# PCE_Joypad_Breakout-v3.net
KiCad netlist of a schematic drawn in EAGLE
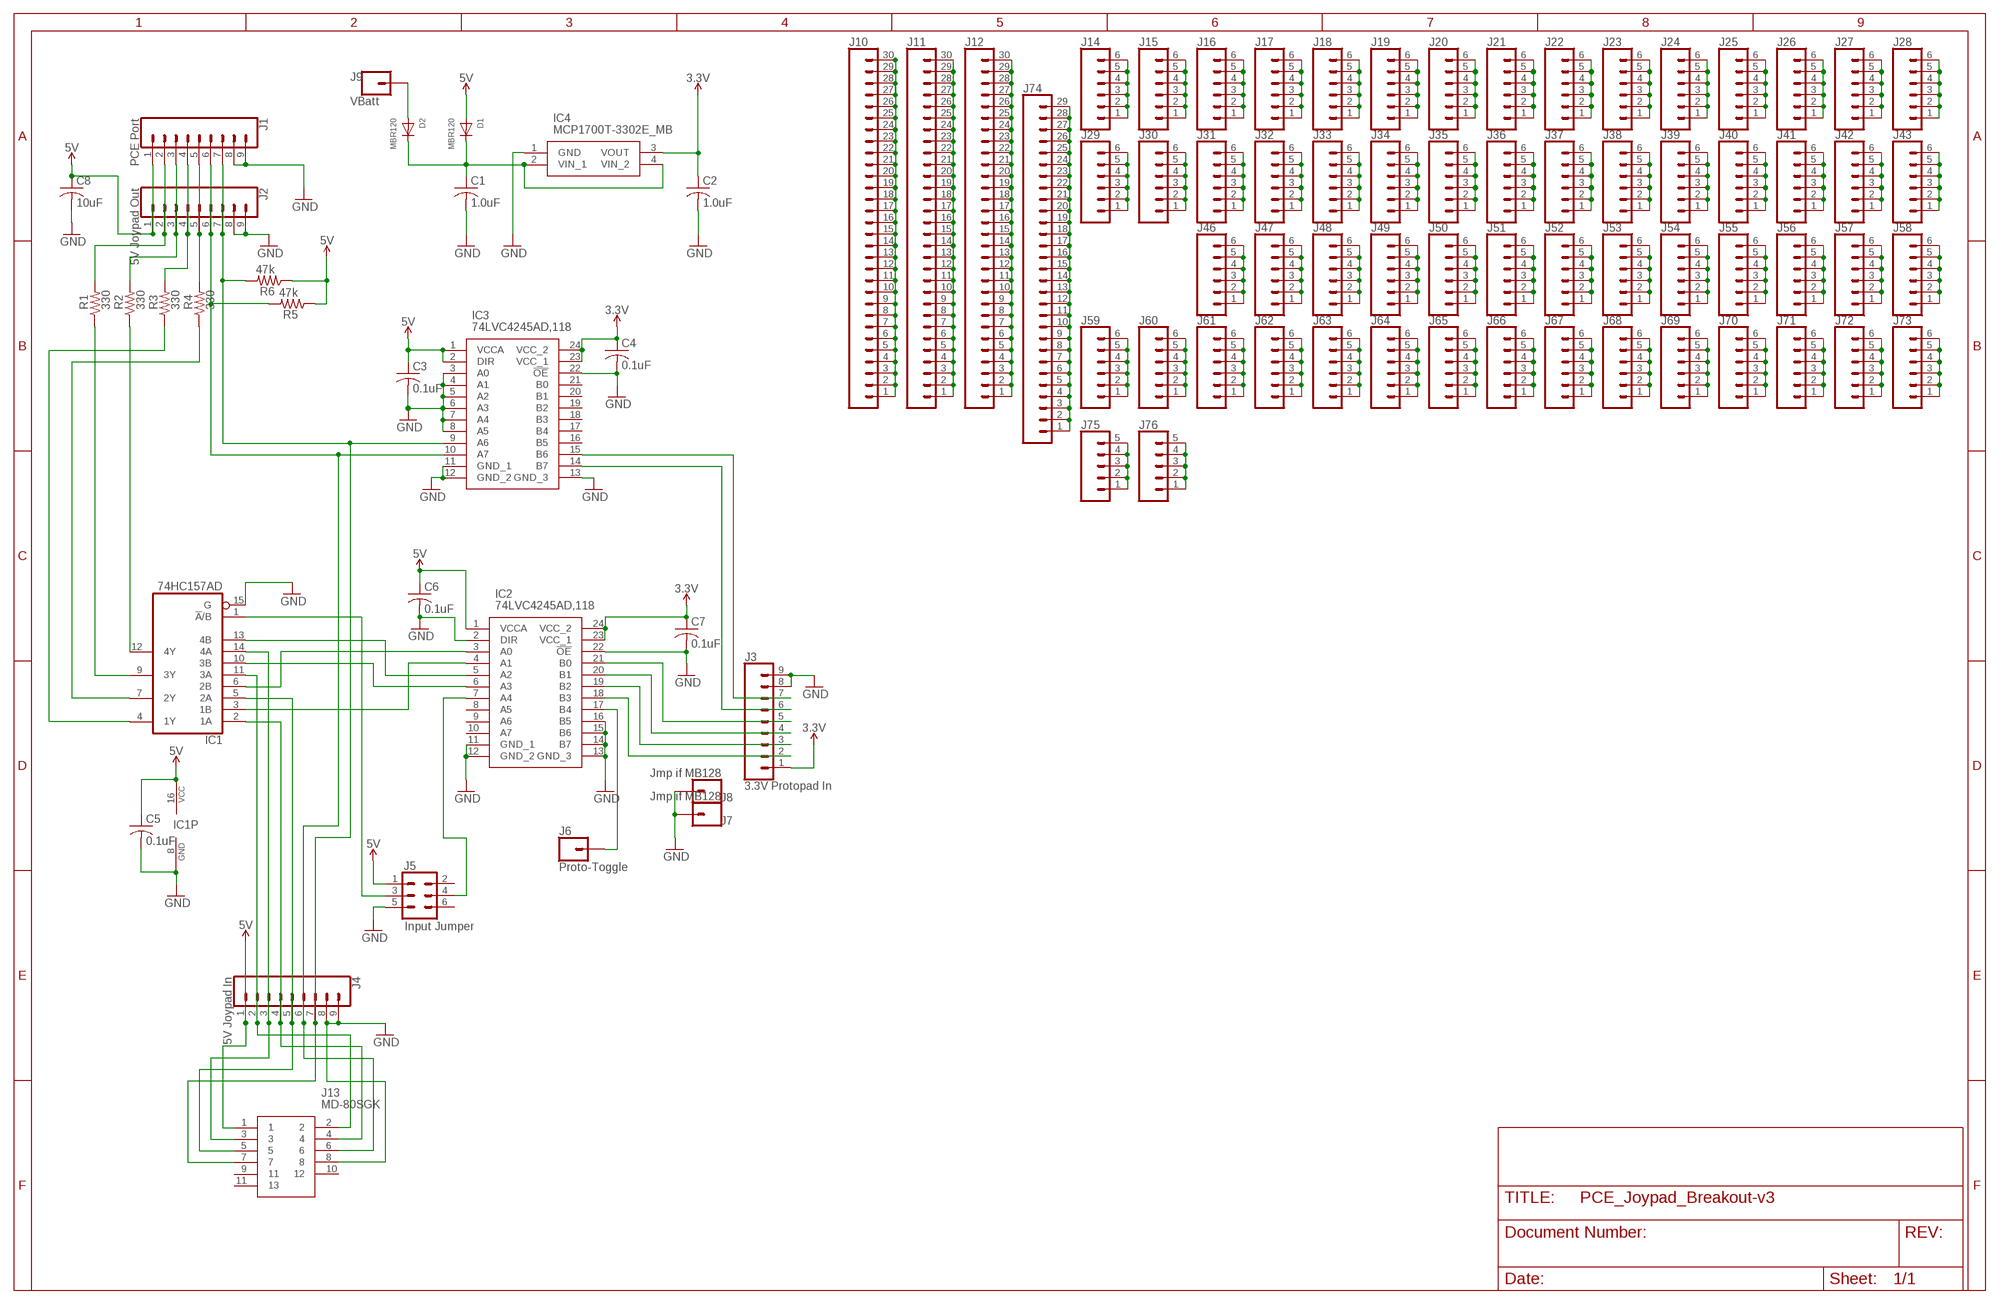
[diagram p0: schematic, sheet 1]

(export (version "E")
  (design (tool "Eeschema 10.0.6"))
  (components
    (comp (ref "C1")
      (value "1.0uF")
      (footprint "eagle-import:C0805")
      (libsource (lib "eagle-import") (part "C-USC0805"))
    )
    (comp (ref "C2")
      (value "1.0uF")
      (footprint "eagle-import:C0805")
      (libsource (lib "eagle-import") (part "C-USC0805"))
    )
    (comp (ref "C3")
      (value "0.1uF")
      (footprint "eagle-import:C0805")
      (libsource (lib "eagle-import") (part "C-USC0805"))
    )
    (comp (ref "C4")
      (value "0.1uF")
      (footprint "eagle-import:C0805")
      (libsource (lib "eagle-import") (part "C-USC0805"))
    )
    (comp (ref "C5")
      (value "0.1uF")
      (footprint "eagle-import:C0805")
      (libsource (lib "eagle-import") (part "C-USC0805"))
    )
    (comp (ref "C6")
      (value "0.1uF")
      (footprint "eagle-import:C0805")
      (libsource (lib "eagle-import") (part "C-USC0805"))
    )
    (comp (ref "C7")
      (value "0.1uF")
      (footprint "eagle-import:C0805")
      (libsource (lib "eagle-import") (part "C-USC0805"))
    )
    (comp (ref "C8")
      (value "10uF")
      (footprint "eagle-import:C0805")
      (libsource (lib "eagle-import") (part "C-USC0805"))
    )
    (comp (ref "D1")
      (value "MBR120")
      (footprint "eagle-import:SOD-123")
      (libsource (lib "eagle-import") (part "DIODESOD-123"))
    )
    (comp (ref "D2")
      (value "MBR120")
      (footprint "eagle-import:SOD-123")
      (libsource (lib "eagle-import") (part "DIODESOD-123"))
    )
    (comp (ref "IC1")
      (value "74HC157AD")
      (footprint "eagle-import:SO16")
      (libsource (lib "eagle-import") (part "74157D"))
    )
    (comp (ref "IC2")
      (value "74LVC4245AD,118")
      (footprint "eagle-import:SOIC127P1032X265-24N")
      (fields
        (field (name "MOUSER_PART_NUMBER") "771-74LVC4245AD-T")
        (field (name "RS_PART_NUMBER") "1708039")
      )
      (libsource (lib "eagle-import") (part "74LVC4245AD,118"))
    )
    (comp (ref "IC3")
      (value "74LVC4245AD,118")
      (footprint "eagle-import:SOIC127P1032X265-24N")
      (fields
        (field (name "MOUSER_PART_NUMBER") "771-74LVC4245AD-T")
        (field (name "RS_PART_NUMBER") "1708039")
      )
      (libsource (lib "eagle-import") (part "74LVC4245AD,118"))
    )
    (comp (ref "IC4")
      (value "MCP1700T-3302E_MB")
      (footprint "eagle-import:MCP1700T-3302E_MB")
      (fields
        (field (name "MANUFACTURER_PART_NUMBER") "MCP1700T-3302E/MB")
        (field (name "MOUSER_PART_NUMBER") "579-MCP1700T3302E/MB")
        (field (name "RS_PART_NUMBER") "9115561")
      )
      (libsource (lib "eagle-import") (part "MCP1700T-3302E_MB"))
    )
    (comp (ref "J1")
      (value "PCE Port")
      (footprint "eagle-import:1X09")
      (libsource (lib "eagle-import") (part "CONN_09"))
    )
    (comp (ref "J2")
      (value "5V Joypad Out")
      (footprint "eagle-import:1X09")
      (libsource (lib "eagle-import") (part "CONN_09"))
    )
    (comp (ref "J3")
      (value "3.3V Protopad In")
      (footprint "eagle-import:1X09")
      (libsource (lib "eagle-import") (part "CONN_09"))
    )
    (comp (ref "J4")
      (value "5V Joypad In")
      (footprint "eagle-import:1X09")
      (libsource (lib "eagle-import") (part "CONN_09"))
    )
    (comp (ref "J5")
      (value "Input Jumper")
      (footprint "eagle-import:2X3")
      (libsource (lib "eagle-import") (part "CONN_03X2FEMALE"))
    )
    (comp (ref "J6")
      (value "Proto-Toggle")
      (footprint "eagle-import:1X01")
      (libsource (lib "eagle-import") (part "CONN_01"))
    )
    (comp (ref "J7")
      (value "Jmp if MB128")
      (footprint "eagle-import:1X01")
      (libsource (lib "eagle-import") (part "CONN_01"))
    )
    (comp (ref "J8")
      (value "Jmp if MB128")
      (footprint "eagle-import:1X01")
      (libsource (lib "eagle-import") (part "CONN_01"))
    )
    (comp (ref "J9")
      (value "VBatt")
      (footprint "eagle-import:1X01")
      (libsource (lib "eagle-import") (part "CONN_01"))
    )
    (comp (ref "J10")
      (value "CONN_30NO_SILK")
      (footprint "eagle-import:1X30_NO_SILK")
      (libsource (lib "eagle-import") (part "CONN_30NO_SILK"))
    )
    (comp (ref "J11")
      (value "CONN_30NO_SILK")
      (footprint "eagle-import:1X30_NO_SILK")
      (libsource (lib "eagle-import") (part "CONN_30NO_SILK"))
    )
    (comp (ref "J12")
      (value "CONN_30NO_SILK")
      (footprint "eagle-import:1X30_NO_SILK")
      (libsource (lib "eagle-import") (part "CONN_30NO_SILK"))
    )
    (comp (ref "J13")
      (value "MD-80SGK")
      (footprint "eagle-import:MD80SGK")
      (fields (field (name "MOUSER_PART_NUMBER") "490-MD-80SGK"))
      (libsource (lib "eagle-import") (part "MD-80SGK"))
    )
    (comp (ref "J14")
      (value "CONN_06NO_SILK_FEMALE_PTH")
      (footprint "eagle-import:1X06_NO_SILK")
      (libsource (lib "eagle-import") (part "CONN_06NO_SILK_FEMALE_PTH"))
    )
    (comp (ref "J15")
      (value "CONN_06NO_SILK_FEMALE_PTH")
      (footprint "eagle-import:1X06_NO_SILK")
      (libsource (lib "eagle-import") (part "CONN_06NO_SILK_FEMALE_PTH"))
    )
    (comp (ref "J16")
      (value "CONN_06NO_SILK_FEMALE_PTH")
      (footprint "eagle-import:1X06_NO_SILK")
      (libsource (lib "eagle-import") (part "CONN_06NO_SILK_FEMALE_PTH"))
    )
    (comp (ref "J17")
      (value "CONN_06NO_SILK_FEMALE_PTH")
      (footprint "eagle-import:1X06_NO_SILK")
      (libsource (lib "eagle-import") (part "CONN_06NO_SILK_FEMALE_PTH"))
    )
    (comp (ref "J18")
      (value "CONN_06NO_SILK_FEMALE_PTH")
      (footprint "eagle-import:1X06_NO_SILK")
      (libsource (lib "eagle-import") (part "CONN_06NO_SILK_FEMALE_PTH"))
    )
    (comp (ref "J19")
      (value "CONN_06NO_SILK_FEMALE_PTH")
      (footprint "eagle-import:1X06_NO_SILK")
      (libsource (lib "eagle-import") (part "CONN_06NO_SILK_FEMALE_PTH"))
    )
    (comp (ref "J20")
      (value "CONN_06NO_SILK_FEMALE_PTH")
      (footprint "eagle-import:1X06_NO_SILK")
      (libsource (lib "eagle-import") (part "CONN_06NO_SILK_FEMALE_PTH"))
    )
    (comp (ref "J21")
      (value "CONN_06NO_SILK_FEMALE_PTH")
      (footprint "eagle-import:1X06_NO_SILK")
      (libsource (lib "eagle-import") (part "CONN_06NO_SILK_FEMALE_PTH"))
    )
    (comp (ref "J22")
      (value "CONN_06NO_SILK_FEMALE_PTH")
      (footprint "eagle-import:1X06_NO_SILK")
      (libsource (lib "eagle-import") (part "CONN_06NO_SILK_FEMALE_PTH"))
    )
    (comp (ref "J23")
      (value "CONN_06NO_SILK_FEMALE_PTH")
      (footprint "eagle-import:1X06_NO_SILK")
      (libsource (lib "eagle-import") (part "CONN_06NO_SILK_FEMALE_PTH"))
    )
    (comp (ref "J24")
      (value "CONN_06NO_SILK_FEMALE_PTH")
      (footprint "eagle-import:1X06_NO_SILK")
      (libsource (lib "eagle-import") (part "CONN_06NO_SILK_FEMALE_PTH"))
    )
    (comp (ref "J25")
      (value "CONN_06NO_SILK_FEMALE_PTH")
      (footprint "eagle-import:1X06_NO_SILK")
      (libsource (lib "eagle-import") (part "CONN_06NO_SILK_FEMALE_PTH"))
    )
    (comp (ref "J26")
      (value "CONN_06NO_SILK_FEMALE_PTH")
      (footprint "eagle-import:1X06_NO_SILK")
      (libsource (lib "eagle-import") (part "CONN_06NO_SILK_FEMALE_PTH"))
    )
    (comp (ref "J27")
      (value "CONN_06NO_SILK_FEMALE_PTH")
      (footprint "eagle-import:1X06_NO_SILK")
      (libsource (lib "eagle-import") (part "CONN_06NO_SILK_FEMALE_PTH"))
    )
    (comp (ref "J28")
      (value "CONN_06NO_SILK_FEMALE_PTH")
      (footprint "eagle-import:1X06_NO_SILK")
      (libsource (lib "eagle-import") (part "CONN_06NO_SILK_FEMALE_PTH"))
    )
    (comp (ref "J29")
      (value "CONN_06NO_SILK_FEMALE_PTH")
      (footprint "eagle-import:1X06_NO_SILK")
      (libsource (lib "eagle-import") (part "CONN_06NO_SILK_FEMALE_PTH"))
    )
    (comp (ref "J30")
      (value "CONN_06NO_SILK_FEMALE_PTH")
      (footprint "eagle-import:1X06_NO_SILK")
      (libsource (lib "eagle-import") (part "CONN_06NO_SILK_FEMALE_PTH"))
    )
    (comp (ref "J31")
      (value "CONN_06NO_SILK_FEMALE_PTH")
      (footprint "eagle-import:1X06_NO_SILK")
      (libsource (lib "eagle-import") (part "CONN_06NO_SILK_FEMALE_PTH"))
    )
    (comp (ref "J32")
      (value "CONN_06NO_SILK_FEMALE_PTH")
      (footprint "eagle-import:1X06_NO_SILK")
      (libsource (lib "eagle-import") (part "CONN_06NO_SILK_FEMALE_PTH"))
    )
    (comp (ref "J33")
      (value "CONN_06NO_SILK_FEMALE_PTH")
      (footprint "eagle-import:1X06_NO_SILK")
      (libsource (lib "eagle-import") (part "CONN_06NO_SILK_FEMALE_PTH"))
    )
    (comp (ref "J34")
      (value "CONN_06NO_SILK_FEMALE_PTH")
      (footprint "eagle-import:1X06_NO_SILK")
      (libsource (lib "eagle-import") (part "CONN_06NO_SILK_FEMALE_PTH"))
    )
    (comp (ref "J35")
      (value "CONN_06NO_SILK_FEMALE_PTH")
      (footprint "eagle-import:1X06_NO_SILK")
      (libsource (lib "eagle-import") (part "CONN_06NO_SILK_FEMALE_PTH"))
    )
    (comp (ref "J36")
      (value "CONN_06NO_SILK_FEMALE_PTH")
      (footprint "eagle-import:1X06_NO_SILK")
      (libsource (lib "eagle-import") (part "CONN_06NO_SILK_FEMALE_PTH"))
    )
    (comp (ref "J37")
      (value "CONN_06NO_SILK_FEMALE_PTH")
      (footprint "eagle-import:1X06_NO_SILK")
      (libsource (lib "eagle-import") (part "CONN_06NO_SILK_FEMALE_PTH"))
    )
    (comp (ref "J38")
      (value "CONN_06NO_SILK_FEMALE_PTH")
      (footprint "eagle-import:1X06_NO_SILK")
      (libsource (lib "eagle-import") (part "CONN_06NO_SILK_FEMALE_PTH"))
    )
    (comp (ref "J39")
      (value "CONN_06NO_SILK_FEMALE_PTH")
      (footprint "eagle-import:1X06_NO_SILK")
      (libsource (lib "eagle-import") (part "CONN_06NO_SILK_FEMALE_PTH"))
    )
    (comp (ref "J40")
      (value "CONN_06NO_SILK_FEMALE_PTH")
      (footprint "eagle-import:1X06_NO_SILK")
      (libsource (lib "eagle-import") (part "CONN_06NO_SILK_FEMALE_PTH"))
    )
    (comp (ref "J41")
      (value "CONN_06NO_SILK_FEMALE_PTH")
      (footprint "eagle-import:1X06_NO_SILK")
      (libsource (lib "eagle-import") (part "CONN_06NO_SILK_FEMALE_PTH"))
    )
    (comp (ref "J42")
      (value "CONN_06NO_SILK_FEMALE_PTH")
      (footprint "eagle-import:1X06_NO_SILK")
      (libsource (lib "eagle-import") (part "CONN_06NO_SILK_FEMALE_PTH"))
    )
    (comp (ref "J43")
      (value "CONN_06NO_SILK_FEMALE_PTH")
      (footprint "eagle-import:1X06_NO_SILK")
      (libsource (lib "eagle-import") (part "CONN_06NO_SILK_FEMALE_PTH"))
    )
    (comp (ref "J46")
      (value "CONN_06NO_SILK_FEMALE_PTH")
      (footprint "eagle-import:1X06_NO_SILK")
      (libsource (lib "eagle-import") (part "CONN_06NO_SILK_FEMALE_PTH"))
    )
    (comp (ref "J47")
      (value "CONN_06NO_SILK_FEMALE_PTH")
      (footprint "eagle-import:1X06_NO_SILK")
      (libsource (lib "eagle-import") (part "CONN_06NO_SILK_FEMALE_PTH"))
    )
    (comp (ref "J48")
      (value "CONN_06NO_SILK_FEMALE_PTH")
      (footprint "eagle-import:1X06_NO_SILK")
      (libsource (lib "eagle-import") (part "CONN_06NO_SILK_FEMALE_PTH"))
    )
    (comp (ref "J49")
      (value "CONN_06NO_SILK_FEMALE_PTH")
      (footprint "eagle-import:1X06_NO_SILK")
      (libsource (lib "eagle-import") (part "CONN_06NO_SILK_FEMALE_PTH"))
    )
    (comp (ref "J50")
      (value "CONN_06NO_SILK_FEMALE_PTH")
      (footprint "eagle-import:1X06_NO_SILK")
      (libsource (lib "eagle-import") (part "CONN_06NO_SILK_FEMALE_PTH"))
    )
    (comp (ref "J51")
      (value "CONN_06NO_SILK_FEMALE_PTH")
      (footprint "eagle-import:1X06_NO_SILK")
      (libsource (lib "eagle-import") (part "CONN_06NO_SILK_FEMALE_PTH"))
    )
    (comp (ref "J52")
      (value "CONN_06NO_SILK_FEMALE_PTH")
      (footprint "eagle-import:1X06_NO_SILK")
      (libsource (lib "eagle-import") (part "CONN_06NO_SILK_FEMALE_PTH"))
    )
    (comp (ref "J53")
      (value "CONN_06NO_SILK_FEMALE_PTH")
      (footprint "eagle-import:1X06_NO_SILK")
      (libsource (lib "eagle-import") (part "CONN_06NO_SILK_FEMALE_PTH"))
    )
    (comp (ref "J54")
      (value "CONN_06NO_SILK_FEMALE_PTH")
      (footprint "eagle-import:1X06_NO_SILK")
      (libsource (lib "eagle-import") (part "CONN_06NO_SILK_FEMALE_PTH"))
    )
    (comp (ref "J55")
      (value "CONN_06NO_SILK_FEMALE_PTH")
      (footprint "eagle-import:1X06_NO_SILK")
      (libsource (lib "eagle-import") (part "CONN_06NO_SILK_FEMALE_PTH"))
    )
    (comp (ref "J56")
      (value "CONN_06NO_SILK_FEMALE_PTH")
      (footprint "eagle-import:1X06_NO_SILK")
      (libsource (lib "eagle-import") (part "CONN_06NO_SILK_FEMALE_PTH"))
    )
    (comp (ref "J57")
      (value "CONN_06NO_SILK_FEMALE_PTH")
      (footprint "eagle-import:1X06_NO_SILK")
      (libsource (lib "eagle-import") (part "CONN_06NO_SILK_FEMALE_PTH"))
    )
    (comp (ref "J58")
      (value "CONN_06NO_SILK_FEMALE_PTH")
      (footprint "eagle-import:1X06_NO_SILK")
      (libsource (lib "eagle-import") (part "CONN_06NO_SILK_FEMALE_PTH"))
    )
    (comp (ref "J59")
      (value "CONN_06NO_SILK_FEMALE_PTH")
      (footprint "eagle-import:1X06_NO_SILK")
      (libsource (lib "eagle-import") (part "CONN_06NO_SILK_FEMALE_PTH"))
    )
    (comp (ref "J60")
      (value "CONN_06NO_SILK_FEMALE_PTH")
      (footprint "eagle-import:1X06_NO_SILK")
      (libsource (lib "eagle-import") (part "CONN_06NO_SILK_FEMALE_PTH"))
    )
    (comp (ref "J61")
      (value "CONN_06NO_SILK_FEMALE_PTH")
      (footprint "eagle-import:1X06_NO_SILK")
      (libsource (lib "eagle-import") (part "CONN_06NO_SILK_FEMALE_PTH"))
    )
    (comp (ref "J62")
      (value "CONN_06NO_SILK_FEMALE_PTH")
      (footprint "eagle-import:1X06_NO_SILK")
      (libsource (lib "eagle-import") (part "CONN_06NO_SILK_FEMALE_PTH"))
    )
    (comp (ref "J63")
      (value "CONN_06NO_SILK_FEMALE_PTH")
      (footprint "eagle-import:1X06_NO_SILK")
      (libsource (lib "eagle-import") (part "CONN_06NO_SILK_FEMALE_PTH"))
    )
    (comp (ref "J64")
      (value "CONN_06NO_SILK_FEMALE_PTH")
      (footprint "eagle-import:1X06_NO_SILK")
      (libsource (lib "eagle-import") (part "CONN_06NO_SILK_FEMALE_PTH"))
    )
    (comp (ref "J65")
      (value "CONN_06NO_SILK_FEMALE_PTH")
      (footprint "eagle-import:1X06_NO_SILK")
      (libsource (lib "eagle-import") (part "CONN_06NO_SILK_FEMALE_PTH"))
    )
    (comp (ref "J66")
      (value "CONN_06NO_SILK_FEMALE_PTH")
      (footprint "eagle-import:1X06_NO_SILK")
      (libsource (lib "eagle-import") (part "CONN_06NO_SILK_FEMALE_PTH"))
    )
    (comp (ref "J67")
      (value "CONN_06NO_SILK_FEMALE_PTH")
      (footprint "eagle-import:1X06_NO_SILK")
      (libsource (lib "eagle-import") (part "CONN_06NO_SILK_FEMALE_PTH"))
    )
    (comp (ref "J68")
      (value "CONN_06NO_SILK_FEMALE_PTH")
      (footprint "eagle-import:1X06_NO_SILK")
      (libsource (lib "eagle-import") (part "CONN_06NO_SILK_FEMALE_PTH"))
    )
    (comp (ref "J69")
      (value "CONN_06NO_SILK_FEMALE_PTH")
      (footprint "eagle-import:1X06_NO_SILK")
      (libsource (lib "eagle-import") (part "CONN_06NO_SILK_FEMALE_PTH"))
    )
    (comp (ref "J70")
      (value "CONN_06NO_SILK_FEMALE_PTH")
      (footprint "eagle-import:1X06_NO_SILK")
      (libsource (lib "eagle-import") (part "CONN_06NO_SILK_FEMALE_PTH"))
    )
    (comp (ref "J71")
      (value "CONN_06NO_SILK_FEMALE_PTH")
      (footprint "eagle-import:1X06_NO_SILK")
      (libsource (lib "eagle-import") (part "CONN_06NO_SILK_FEMALE_PTH"))
    )
    (comp (ref "J72")
      (value "CONN_06NO_SILK_FEMALE_PTH")
      (footprint "eagle-import:1X06_NO_SILK")
      (libsource (lib "eagle-import") (part "CONN_06NO_SILK_FEMALE_PTH"))
    )
    (comp (ref "J73")
      (value "CONN_06NO_SILK_FEMALE_PTH")
      (footprint "eagle-import:1X06_NO_SILK")
      (libsource (lib "eagle-import") (part "CONN_06NO_SILK_FEMALE_PTH"))
    )
    (comp (ref "J74")
      (value "CONN_29NO_SILK")
      (footprint "eagle-import:1X29_NO_SILK")
      (libsource (lib "eagle-import") (part "CONN_29NO_SILK"))
    )
    (comp (ref "J75")
      (value "CONN_05NO_SILK")
      (footprint "eagle-import:1X05_NO_SILK")
      (libsource (lib "eagle-import") (part "CONN_05NO_SILK"))
    )
    (comp (ref "J76")
      (value "CONN_05NO_SILK")
      (footprint "eagle-import:1X05_NO_SILK")
      (libsource (lib "eagle-import") (part "CONN_05NO_SILK"))
    )
    (comp (ref "R1")
      (value "330")
      (footprint "eagle-import:R0805")
      (libsource (lib "eagle-import") (part "R-US_R0805"))
    )
    (comp (ref "R2")
      (value "330")
      (footprint "eagle-import:R0805")
      (libsource (lib "eagle-import") (part "R-US_R0805"))
    )
    (comp (ref "R3")
      (value "330")
      (footprint "eagle-import:R0805")
      (libsource (lib "eagle-import") (part "R-US_R0805"))
    )
    (comp (ref "R4")
      (value "330")
      (footprint "eagle-import:R0805")
      (libsource (lib "eagle-import") (part "R-US_R0805"))
    )
    (comp (ref "R5")
      (value "47k")
      (footprint "eagle-import:R0805")
      (libsource (lib "eagle-import") (part "R-US_R0805"))
    )
    (comp (ref "R6")
      (value "47k")
      (footprint "eagle-import:R0805")
      (libsource (lib "eagle-import") (part "R-US_R0805"))
    )
  )
  (nets
    (net (code "1") (name "3.3V") (class "Default")
      (node (ref "C2") (pin "1") (pinfunction "1_1") (pintype "passive"))
      (node (ref "C4") (pin "1") (pinfunction "1_1") (pintype "passive"))
      (node (ref "C7") (pin "1") (pinfunction "1_1") (pintype "passive"))
      (node (ref "IC2") (pin "23") (pinfunction "VCC_1_23") (pintype "bidirectional"))
      (node (ref "IC2") (pin "24") (pinfunction "VCC_2_24") (pintype "bidirectional"))
      (node (ref "IC3") (pin "23") (pinfunction "VCC_1_23") (pintype "bidirectional"))
      (node (ref "IC3") (pin "24") (pinfunction "VCC_2_24") (pintype "bidirectional"))
      (node (ref "IC4") (pin "3") (pinfunction "VOUT_3") (pintype "output"))
      (node (ref "J3") (pin "1") (pinfunction "1_1") (pintype "passive"))
    )
    (net (code "2") (name "5V") (class "Default")
      (node (ref "C3") (pin "1") (pinfunction "1_1") (pintype "passive"))
      (node (ref "C5") (pin "1") (pinfunction "1_1") (pintype "passive"))
      (node (ref "C6") (pin "1") (pinfunction "1_1") (pintype "passive"))
      (node (ref "C8") (pin "1") (pinfunction "1_1") (pintype "passive"))
      (node (ref "D1") (pin "A") (pinfunction "A_A") (pintype "passive"))
      (node (ref "IC1") (pin "16") (pinfunction "VCC_16") (pintype "power_in"))
      (node (ref "IC2") (pin "1") (pinfunction "VCCA_1") (pintype "bidirectional"))
      (node (ref "IC3") (pin "1") (pinfunction "VCCA_1") (pintype "bidirectional"))
      (node (ref "IC3") (pin "2") (pinfunction "DIR_2") (pintype "bidirectional"))
      (node (ref "J1") (pin "1") (pinfunction "1_1") (pintype "passive"))
      (node (ref "J13") (pin "1") (pinfunction "1_1") (pintype "bidirectional"))
      (node (ref "J2") (pin "1") (pinfunction "1_1") (pintype "passive"))
      (node (ref "J4") (pin "1") (pinfunction "1_1") (pintype "passive"))
      (node (ref "J5") (pin "1") (pinfunction "1_1") (pintype "bidirectional"))
      (node (ref "R5") (pin "1") (pinfunction "1_1") (pintype "passive"))
      (node (ref "R6") (pin "1") (pinfunction "1_1") (pintype "passive"))
    )
    (net (code "3") (name "GND") (class "Default")
      (node (ref "C1") (pin "2") (pinfunction "2_2") (pintype "passive"))
      (node (ref "C2") (pin "2") (pinfunction "2_2") (pintype "passive"))
      (node (ref "C3") (pin "2") (pinfunction "2_2") (pintype "passive"))
      (node (ref "C4") (pin "2") (pinfunction "2_2") (pintype "passive"))
      (node (ref "C5") (pin "2") (pinfunction "2_2") (pintype "passive"))
      (node (ref "C6") (pin "2") (pinfunction "2_2") (pintype "passive"))
      (node (ref "C7") (pin "2") (pinfunction "2_2") (pintype "passive"))
      (node (ref "C8") (pin "2") (pinfunction "2_2") (pintype "passive"))
      (node (ref "IC1") (pin "15") (pinfunction "G_15") (pintype "input"))
      (node (ref "IC1") (pin "8") (pinfunction "GND_8") (pintype "power_in"))
      (node (ref "IC2") (pin "11") (pinfunction "GND_1_11") (pintype "bidirectional"))
      (node (ref "IC2") (pin "12") (pinfunction "GND_2_12") (pintype "bidirectional"))
      (node (ref "IC2") (pin "13") (pinfunction "GND_3_13") (pintype "bidirectional"))
      (node (ref "IC2") (pin "14") (pinfunction "B7_14") (pintype "bidirectional"))
      (node (ref "IC2") (pin "15") (pinfunction "B6_15") (pintype "bidirectional"))
      (node (ref "IC2") (pin "16") (pinfunction "B5_16") (pintype "bidirectional"))
      (node (ref "IC2") (pin "2") (pinfunction "DIR_2") (pintype "bidirectional"))
      (node (ref "IC2") (pin "22") (pinfunction "~{OE}_22") (pintype "bidirectional"))
      (node (ref "IC3") (pin "11") (pinfunction "GND_1_11") (pintype "bidirectional"))
      (node (ref "IC3") (pin "12") (pinfunction "GND_2_12") (pintype "bidirectional"))
      (node (ref "IC3") (pin "13") (pinfunction "GND_3_13") (pintype "bidirectional"))
      (node (ref "IC3") (pin "22") (pinfunction "~{OE}_22") (pintype "bidirectional"))
      (node (ref "IC3") (pin "3") (pinfunction "A0_3") (pintype "bidirectional"))
      (node (ref "IC3") (pin "4") (pinfunction "A1_4") (pintype "bidirectional"))
      (node (ref "IC3") (pin "5") (pinfunction "A2_5") (pintype "bidirectional"))
      (node (ref "IC3") (pin "6") (pinfunction "A3_6") (pintype "bidirectional"))
      (node (ref "IC3") (pin "7") (pinfunction "A4_7") (pintype "bidirectional"))
      (node (ref "IC3") (pin "8") (pinfunction "A5_8") (pintype "bidirectional"))
      (node (ref "IC4") (pin "1") (pinfunction "GND_1") (pintype "power_in"))
      (node (ref "J1") (pin "8") (pinfunction "8_8") (pintype "passive"))
      (node (ref "J1") (pin "9") (pinfunction "9_9") (pintype "passive"))
      (node (ref "J13") (pin "8") (pinfunction "8_8") (pintype "bidirectional"))
      (node (ref "J2") (pin "8") (pinfunction "8_8") (pintype "passive"))
      (node (ref "J2") (pin "9") (pinfunction "9_9") (pintype "passive"))
      (node (ref "J3") (pin "8") (pinfunction "8_8") (pintype "passive"))
      (node (ref "J3") (pin "9") (pinfunction "9_9") (pintype "passive"))
      (node (ref "J4") (pin "8") (pinfunction "8_8") (pintype "passive"))
      (node (ref "J4") (pin "9") (pinfunction "9_9") (pintype "passive"))
      (node (ref "J5") (pin "5") (pinfunction "5_5") (pintype "bidirectional"))
      (node (ref "J7") (pin "1") (pinfunction "1_1") (pintype "passive"))
      (node (ref "J8") (pin "1") (pinfunction "1_1") (pintype "passive"))
    )
    (net (code "4") (name "Net-(D2-PadA)") (class "Default")
      (node (ref "D2") (pin "A") (pinfunction "A_A") (pintype "passive"))
      (node (ref "J9") (pin "1") (pinfunction "1_1") (pintype "passive"))
    )
    (net (code "5") (name "Net-(IC1A-1A)") (class "Default")
      (node (ref "IC1") (pin "2") (pinfunction "1A_2") (pintype "input"))
      (node (ref "J13") (pin "4") (pinfunction "4_4") (pintype "bidirectional"))
      (node (ref "J4") (pin "4") (pinfunction "4_4") (pintype "passive"))
    )
    (net (code "6") (name "Net-(IC1A-1B)") (class "Default")
      (node (ref "IC1") (pin "3") (pinfunction "1B_3") (pintype "input"))
      (node (ref "IC2") (pin "4") (pinfunction "A1_4") (pintype "bidirectional"))
    )
    (net (code "7") (name "Net-(IC1A-1Y)") (class "Default")
      (node (ref "IC1") (pin "4") (pinfunction "1Y_4") (pintype "output"))
      (node (ref "R3") (pin "1") (pinfunction "1_1") (pintype "passive"))
    )
    (net (code "8") (name "Net-(IC1A-2A)") (class "Default")
      (node (ref "IC1") (pin "5") (pinfunction "2A_5") (pintype "input"))
      (node (ref "J13") (pin "5") (pinfunction "5_5") (pintype "bidirectional"))
      (node (ref "J4") (pin "5") (pinfunction "5_5") (pintype "passive"))
    )
    (net (code "9") (name "Net-(IC1A-2B)") (class "Default")
      (node (ref "IC1") (pin "6") (pinfunction "2B_6") (pintype "input"))
      (node (ref "IC2") (pin "3") (pinfunction "A0_3") (pintype "bidirectional"))
    )
    (net (code "10") (name "Net-(IC1A-2Y)") (class "Default")
      (node (ref "IC1") (pin "7") (pinfunction "2Y_7") (pintype "output"))
      (node (ref "R4") (pin "1") (pinfunction "1_1") (pintype "passive"))
    )
    (net (code "11") (name "Net-(IC1A-3A)") (class "Default")
      (node (ref "IC1") (pin "11") (pinfunction "3A_11") (pintype "input"))
      (node (ref "J13") (pin "2") (pinfunction "2_2") (pintype "bidirectional"))
      (node (ref "J4") (pin "2") (pinfunction "2_2") (pintype "passive"))
    )
    (net (code "12") (name "Net-(IC1A-3B)") (class "Default")
      (node (ref "IC1") (pin "10") (pinfunction "3B_10") (pintype "input"))
      (node (ref "IC2") (pin "6") (pinfunction "A3_6") (pintype "bidirectional"))
    )
    (net (code "13") (name "Net-(IC1A-3Y)") (class "Default")
      (node (ref "IC1") (pin "9") (pinfunction "3Y_9") (pintype "output"))
      (node (ref "R1") (pin "1") (pinfunction "1_1") (pintype "passive"))
    )
    (net (code "14") (name "Net-(IC1A-4A)") (class "Default")
      (node (ref "IC1") (pin "14") (pinfunction "4A_14") (pintype "input"))
      (node (ref "J13") (pin "3") (pinfunction "3_3") (pintype "bidirectional"))
      (node (ref "J4") (pin "3") (pinfunction "3_3") (pintype "passive"))
    )
    (net (code "15") (name "Net-(IC1A-4B)") (class "Default")
      (node (ref "IC1") (pin "13") (pinfunction "4B_13") (pintype "input"))
      (node (ref "IC2") (pin "5") (pinfunction "A2_5") (pintype "bidirectional"))
    )
    (net (code "16") (name "Net-(IC1A-4Y)") (class "Default")
      (node (ref "IC1") (pin "12") (pinfunction "4Y_12") (pintype "output"))
      (node (ref "R2") (pin "1") (pinfunction "1_1") (pintype "passive"))
    )
    (net (code "17") (name "Net-(IC1A-~{A}{slash}B)") (class "Default")
      (node (ref "IC1") (pin "1") (pinfunction "~{A}/B_1") (pintype "input"))
      (node (ref "J5") (pin "3") (pinfunction "3_3") (pintype "bidirectional"))
    )
    (net (code "18") (name "Net-(IC2-A4)") (class "Default")
      (node (ref "IC2") (pin "7") (pinfunction "A4_7") (pintype "bidirectional"))
      (node (ref "J5") (pin "4") (pinfunction "4_4") (pintype "bidirectional"))
    )
    (net (code "19") (name "Net-(IC2-B0)") (class "Default")
      (node (ref "IC2") (pin "21") (pinfunction "B0_21") (pintype "bidirectional"))
      (node (ref "J3") (pin "5") (pinfunction "5_5") (pintype "passive"))
    )
    (net (code "20") (name "Net-(IC2-B1)") (class "Default")
      (node (ref "IC2") (pin "20") (pinfunction "B1_20") (pintype "bidirectional"))
      (node (ref "J3") (pin "4") (pinfunction "4_4") (pintype "passive"))
    )
    (net (code "21") (name "Net-(IC2-B2)") (class "Default")
      (node (ref "IC2") (pin "19") (pinfunction "B2_19") (pintype "bidirectional"))
      (node (ref "J3") (pin "3") (pinfunction "3_3") (pintype "passive"))
    )
    (net (code "22") (name "Net-(IC2-B3)") (class "Default")
      (node (ref "IC2") (pin "18") (pinfunction "B3_18") (pintype "bidirectional"))
      (node (ref "J3") (pin "2") (pinfunction "2_2") (pintype "passive"))
    )
    (net (code "23") (name "Net-(IC2-B4)") (class "Default")
      (node (ref "IC2") (pin "17") (pinfunction "B4_17") (pintype "bidirectional"))
      (node (ref "J6") (pin "1") (pinfunction "1_1") (pintype "passive"))
    )
    (net (code "24") (name "Net-(IC3-A6)") (class "Default")
      (node (ref "IC3") (pin "9") (pinfunction "A6_9") (pintype "bidirectional"))
      (node (ref "J1") (pin "7") (pinfunction "7_7") (pintype "passive"))
      (node (ref "J13") (pin "7") (pinfunction "7_7") (pintype "bidirectional"))
      (node (ref "J2") (pin "7") (pinfunction "7_7") (pintype "passive"))
      (node (ref "J4") (pin "7") (pinfunction "7_7") (pintype "passive"))
      (node (ref "R6") (pin "2") (pinfunction "2_2") (pintype "passive"))
    )
    (net (code "25") (name "Net-(IC3-A7)") (class "Default")
      (node (ref "IC3") (pin "10") (pinfunction "A7_10") (pintype "bidirectional"))
      (node (ref "J1") (pin "6") (pinfunction "6_6") (pintype "passive"))
      (node (ref "J13") (pin "6") (pinfunction "6_6") (pintype "bidirectional"))
      (node (ref "J2") (pin "6") (pinfunction "6_6") (pintype "passive"))
      (node (ref "J4") (pin "6") (pinfunction "6_6") (pintype "passive"))
      (node (ref "R5") (pin "2") (pinfunction "2_2") (pintype "passive"))
    )
    (net (code "26") (name "Net-(IC3-B6)") (class "Default")
      (node (ref "IC3") (pin "15") (pinfunction "B6_15") (pintype "bidirectional"))
      (node (ref "J3") (pin "7") (pinfunction "7_7") (pintype "passive"))
    )
    (net (code "27") (name "Net-(IC3-B7)") (class "Default")
      (node (ref "IC3") (pin "14") (pinfunction "B7_14") (pintype "bidirectional"))
      (node (ref "J3") (pin "6") (pinfunction "6_6") (pintype "passive"))
    )
    (net (code "28") (name "Net-(IC4-VIN_1)") (class "Default")
      (node (ref "C1") (pin "1") (pinfunction "1_1") (pintype "passive"))
      (node (ref "D1") (pin "C") (pinfunction "C_C") (pintype "passive"))
      (node (ref "D2") (pin "C") (pinfunction "C_C") (pintype "passive"))
      (node (ref "IC4") (pin "2") (pinfunction "VIN_1_2") (pintype "input"))
      (node (ref "IC4") (pin "4") (pinfunction "VIN_2_4") (pintype "bidirectional"))
    )
    (net (code "29") (name "Net-(J1-Pad2)") (class "Default")
      (node (ref "J1") (pin "2") (pinfunction "2_2") (pintype "passive"))
      (node (ref "J2") (pin "2") (pinfunction "2_2") (pintype "passive"))
      (node (ref "R1") (pin "2") (pinfunction "2_2") (pintype "passive"))
    )
    (net (code "30") (name "Net-(J1-Pad3)") (class "Default")
      (node (ref "J1") (pin "3") (pinfunction "3_3") (pintype "passive"))
      (node (ref "J2") (pin "3") (pinfunction "3_3") (pintype "passive"))
      (node (ref "R2") (pin "2") (pinfunction "2_2") (pintype "passive"))
    )
    (net (code "31") (name "Net-(J1-Pad4)") (class "Default")
      (node (ref "J1") (pin "4") (pinfunction "4_4") (pintype "passive"))
      (node (ref "J2") (pin "4") (pinfunction "4_4") (pintype "passive"))
      (node (ref "R3") (pin "2") (pinfunction "2_2") (pintype "passive"))
    )
    (net (code "32") (name "Net-(J1-Pad5)") (class "Default")
      (node (ref "J1") (pin "5") (pinfunction "5_5") (pintype "passive"))
      (node (ref "J2") (pin "5") (pinfunction "5_5") (pintype "passive"))
      (node (ref "R4") (pin "2") (pinfunction "2_2") (pintype "passive"))
    )
    (net (code "33") (name "Net-(J10-Pad1)") (class "Default")
      (node (ref "J10") (pin "1") (pinfunction "1_1") (pintype "passive"))
      (node (ref "J10") (pin "10") (pinfunction "10_10") (pintype "passive"))
      (node (ref "J10") (pin "11") (pinfunction "11_11") (pintype "passive"))
      (node (ref "J10") (pin "12") (pinfunction "12_12") (pintype "passive"))
      (node (ref "J10") (pin "13") (pinfunction "13_13") (pintype "passive"))
      (node (ref "J10") (pin "14") (pinfunction "14_14") (pintype "passive"))
      (node (ref "J10") (pin "15") (pinfunction "15_15") (pintype "passive"))
      (node (ref "J10") (pin "16") (pinfunction "16_16") (pintype "passive"))
      (node (ref "J10") (pin "17") (pinfunction "17_17") (pintype "passive"))
      (node (ref "J10") (pin "18") (pinfunction "18_18") (pintype "passive"))
      (node (ref "J10") (pin "19") (pinfunction "19_19") (pintype "passive"))
      (node (ref "J10") (pin "2") (pinfunction "2_2") (pintype "passive"))
      (node (ref "J10") (pin "20") (pinfunction "20_20") (pintype "passive"))
      (node (ref "J10") (pin "21") (pinfunction "21_21") (pintype "passive"))
      (node (ref "J10") (pin "22") (pinfunction "22_22") (pintype "passive"))
      (node (ref "J10") (pin "23") (pinfunction "23_23") (pintype "passive"))
      (node (ref "J10") (pin "24") (pinfunction "24_24") (pintype "passive"))
      (node (ref "J10") (pin "25") (pinfunction "25_25") (pintype "passive"))
      (node (ref "J10") (pin "26") (pinfunction "26_26") (pintype "passive"))
      (node (ref "J10") (pin "27") (pinfunction "27_27") (pintype "passive"))
      (node (ref "J10") (pin "28") (pinfunction "28_28") (pintype "passive"))
      (node (ref "J10") (pin "29") (pinfunction "29_29") (pintype "passive"))
      (node (ref "J10") (pin "3") (pinfunction "3_3") (pintype "passive"))
      (node (ref "J10") (pin "30") (pinfunction "30_30") (pintype "passive"))
      (node (ref "J10") (pin "4") (pinfunction "4_4") (pintype "passive"))
      (node (ref "J10") (pin "5") (pinfunction "5_5") (pintype "passive"))
      (node (ref "J10") (pin "6") (pinfunction "6_6") (pintype "passive"))
      (node (ref "J10") (pin "7") (pinfunction "7_7") (pintype "passive"))
      (node (ref "J10") (pin "8") (pinfunction "8_8") (pintype "passive"))
      (node (ref "J10") (pin "9") (pinfunction "9_9") (pintype "passive"))
    )
    (net (code "34") (name "Net-(J11-Pad1)") (class "Default")
      (node (ref "J11") (pin "1") (pinfunction "1_1") (pintype "passive"))
      (node (ref "J11") (pin "10") (pinfunction "10_10") (pintype "passive"))
      (node (ref "J11") (pin "11") (pinfunction "11_11") (pintype "passive"))
      (node (ref "J11") (pin "12") (pinfunction "12_12") (pintype "passive"))
      (node (ref "J11") (pin "13") (pinfunction "13_13") (pintype "passive"))
      (node (ref "J11") (pin "14") (pinfunction "14_14") (pintype "passive"))
      (node (ref "J11") (pin "15") (pinfunction "15_15") (pintype "passive"))
      (node (ref "J11") (pin "16") (pinfunction "16_16") (pintype "passive"))
      (node (ref "J11") (pin "17") (pinfunction "17_17") (pintype "passive"))
      (node (ref "J11") (pin "18") (pinfunction "18_18") (pintype "passive"))
      (node (ref "J11") (pin "19") (pinfunction "19_19") (pintype "passive"))
      (node (ref "J11") (pin "2") (pinfunction "2_2") (pintype "passive"))
      (node (ref "J11") (pin "20") (pinfunction "20_20") (pintype "passive"))
      (node (ref "J11") (pin "21") (pinfunction "21_21") (pintype "passive"))
      (node (ref "J11") (pin "22") (pinfunction "22_22") (pintype "passive"))
      (node (ref "J11") (pin "23") (pinfunction "23_23") (pintype "passive"))
      (node (ref "J11") (pin "24") (pinfunction "24_24") (pintype "passive"))
      (node (ref "J11") (pin "25") (pinfunction "25_25") (pintype "passive"))
      (node (ref "J11") (pin "26") (pinfunction "26_26") (pintype "passive"))
      (node (ref "J11") (pin "27") (pinfunction "27_27") (pintype "passive"))
      (node (ref "J11") (pin "28") (pinfunction "28_28") (pintype "passive"))
      (node (ref "J11") (pin "29") (pinfunction "29_29") (pintype "passive"))
      (node (ref "J11") (pin "3") (pinfunction "3_3") (pintype "passive"))
      (node (ref "J11") (pin "30") (pinfunction "30_30") (pintype "passive"))
      (node (ref "J11") (pin "4") (pinfunction "4_4") (pintype "passive"))
      (node (ref "J11") (pin "5") (pinfunction "5_5") (pintype "passive"))
      (node (ref "J11") (pin "6") (pinfunction "6_6") (pintype "passive"))
      (node (ref "J11") (pin "7") (pinfunction "7_7") (pintype "passive"))
      (node (ref "J11") (pin "8") (pinfunction "8_8") (pintype "passive"))
      (node (ref "J11") (pin "9") (pinfunction "9_9") (pintype "passive"))
    )
    (net (code "35") (name "Net-(J12-Pad1)") (class "Default")
      (node (ref "J12") (pin "1") (pinfunction "1_1") (pintype "passive"))
      (node (ref "J12") (pin "10") (pinfunction "10_10") (pintype "passive"))
      (node (ref "J12") (pin "11") (pinfunction "11_11") (pintype "passive"))
      (node (ref "J12") (pin "12") (pinfunction "12_12") (pintype "passive"))
      (node (ref "J12") (pin "13") (pinfunction "13_13") (pintype "passive"))
      (node (ref "J12") (pin "14") (pinfunction "14_14") (pintype "passive"))
      (node (ref "J12") (pin "15") (pinfunction "15_15") (pintype "passive"))
      (node (ref "J12") (pin "16") (pinfunction "16_16") (pintype "passive"))
      (node (ref "J12") (pin "17") (pinfunction "17_17") (pintype "passive"))
      (node (ref "J12") (pin "18") (pinfunction "18_18") (pintype "passive"))
      (node (ref "J12") (pin "19") (pinfunction "19_19") (pintype "passive"))
      (node (ref "J12") (pin "2") (pinfunction "2_2") (pintype "passive"))
      (node (ref "J12") (pin "20") (pinfunction "20_20") (pintype "passive"))
      (node (ref "J12") (pin "21") (pinfunction "21_21") (pintype "passive"))
      (node (ref "J12") (pin "22") (pinfunction "22_22") (pintype "passive"))
      (node (ref "J12") (pin "23") (pinfunction "23_23") (pintype "passive"))
      (node (ref "J12") (pin "24") (pinfunction "24_24") (pintype "passive"))
      (node (ref "J12") (pin "25") (pinfunction "25_25") (pintype "passive"))
      (node (ref "J12") (pin "26") (pinfunction "26_26") (pintype "passive"))
      (node (ref "J12") (pin "27") (pinfunction "27_27") (pintype "passive"))
      (node (ref "J12") (pin "28") (pinfunction "28_28") (pintype "passive"))
      (node (ref "J12") (pin "29") (pinfunction "29_29") (pintype "passive"))
      (node (ref "J12") (pin "3") (pinfunction "3_3") (pintype "passive"))
      (node (ref "J12") (pin "30") (pinfunction "30_30") (pintype "passive"))
      (node (ref "J12") (pin "4") (pinfunction "4_4") (pintype "passive"))
      (node (ref "J12") (pin "5") (pinfunction "5_5") (pintype "passive"))
      (node (ref "J12") (pin "6") (pinfunction "6_6") (pintype "passive"))
      (node (ref "J12") (pin "7") (pinfunction "7_7") (pintype "passive"))
      (node (ref "J12") (pin "8") (pinfunction "8_8") (pintype "passive"))
      (node (ref "J12") (pin "9") (pinfunction "9_9") (pintype "passive"))
    )
    (net (code "36") (name "Net-(J14-Pad1)") (class "Default")
      (node (ref "J14") (pin "1") (pinfunction "1_1") (pintype "passive"))
      (node (ref "J14") (pin "2") (pinfunction "2_2") (pintype "passive"))
      (node (ref "J14") (pin "3") (pinfunction "3_3") (pintype "passive"))
      (node (ref "J14") (pin "4") (pinfunction "4_4") (pintype "passive"))
      (node (ref "J14") (pin "5") (pinfunction "5_5") (pintype "passive"))
      (node (ref "J14") (pin "6") (pinfunction "6_6") (pintype "passive"))
    )
    (net (code "37") (name "Net-(J15-Pad1)") (class "Default")
      (node (ref "J15") (pin "1") (pinfunction "1_1") (pintype "passive"))
      (node (ref "J15") (pin "2") (pinfunction "2_2") (pintype "passive"))
      (node (ref "J15") (pin "3") (pinfunction "3_3") (pintype "passive"))
      (node (ref "J15") (pin "4") (pinfunction "4_4") (pintype "passive"))
      (node (ref "J15") (pin "5") (pinfunction "5_5") (pintype "passive"))
      (node (ref "J15") (pin "6") (pinfunction "6_6") (pintype "passive"))
    )
    (net (code "38") (name "Net-(J16-Pad1)") (class "Default")
      (node (ref "J16") (pin "1") (pinfunction "1_1") (pintype "passive"))
      (node (ref "J16") (pin "2") (pinfunction "2_2") (pintype "passive"))
      (node (ref "J16") (pin "3") (pinfunction "3_3") (pintype "passive"))
      (node (ref "J16") (pin "4") (pinfunction "4_4") (pintype "passive"))
      (node (ref "J16") (pin "5") (pinfunction "5_5") (pintype "passive"))
      (node (ref "J16") (pin "6") (pinfunction "6_6") (pintype "passive"))
    )
    (net (code "39") (name "Net-(J17-Pad1)") (class "Default")
      (node (ref "J17") (pin "1") (pinfunction "1_1") (pintype "passive"))
      (node (ref "J17") (pin "2") (pinfunction "2_2") (pintype "passive"))
      (node (ref "J17") (pin "3") (pinfunction "3_3") (pintype "passive"))
      (node (ref "J17") (pin "4") (pinfunction "4_4") (pintype "passive"))
      (node (ref "J17") (pin "5") (pinfunction "5_5") (pintype "passive"))
      (node (ref "J17") (pin "6") (pinfunction "6_6") (pintype "passive"))
    )
    (net (code "40") (name "Net-(J18-Pad1)") (class "Default")
      (node (ref "J18") (pin "1") (pinfunction "1_1") (pintype "passive"))
      (node (ref "J18") (pin "2") (pinfunction "2_2") (pintype "passive"))
      (node (ref "J18") (pin "3") (pinfunction "3_3") (pintype "passive"))
      (node (ref "J18") (pin "4") (pinfunction "4_4") (pintype "passive"))
      (node (ref "J18") (pin "5") (pinfunction "5_5") (pintype "passive"))
      (node (ref "J18") (pin "6") (pinfunction "6_6") (pintype "passive"))
    )
    (net (code "41") (name "Net-(J19-Pad1)") (class "Default")
      (node (ref "J19") (pin "1") (pinfunction "1_1") (pintype "passive"))
      (node (ref "J19") (pin "2") (pinfunction "2_2") (pintype "passive"))
      (node (ref "J19") (pin "3") (pinfunction "3_3") (pintype "passive"))
      (node (ref "J19") (pin "4") (pinfunction "4_4") (pintype "passive"))
      (node (ref "J19") (pin "5") (pinfunction "5_5") (pintype "passive"))
      (node (ref "J19") (pin "6") (pinfunction "6_6") (pintype "passive"))
    )
    (net (code "42") (name "Net-(J20-Pad1)") (class "Default")
      (node (ref "J20") (pin "1") (pinfunction "1_1") (pintype "passive"))
      (node (ref "J20") (pin "2") (pinfunction "2_2") (pintype "passive"))
      (node (ref "J20") (pin "3") (pinfunction "3_3") (pintype "passive"))
      (node (ref "J20") (pin "4") (pinfunction "4_4") (pintype "passive"))
      (node (ref "J20") (pin "5") (pinfunction "5_5") (pintype "passive"))
      (node (ref "J20") (pin "6") (pinfunction "6_6") (pintype "passive"))
    )
    (net (code "43") (name "Net-(J21-Pad1)") (class "Default")
      (node (ref "J21") (pin "1") (pinfunction "1_1") (pintype "passive"))
      (node (ref "J21") (pin "2") (pinfunction "2_2") (pintype "passive"))
      (node (ref "J21") (pin "3") (pinfunction "3_3") (pintype "passive"))
      (node (ref "J21") (pin "4") (pinfunction "4_4") (pintype "passive"))
      (node (ref "J21") (pin "5") (pinfunction "5_5") (pintype "passive"))
      (node (ref "J21") (pin "6") (pinfunction "6_6") (pintype "passive"))
    )
    (net (code "44") (name "Net-(J22-Pad1)") (class "Default")
      (node (ref "J22") (pin "1") (pinfunction "1_1") (pintype "passive"))
      (node (ref "J22") (pin "2") (pinfunction "2_2") (pintype "passive"))
      (node (ref "J22") (pin "3") (pinfunction "3_3") (pintype "passive"))
      (node (ref "J22") (pin "4") (pinfunction "4_4") (pintype "passive"))
      (node (ref "J22") (pin "5") (pinfunction "5_5") (pintype "passive"))
      (node (ref "J22") (pin "6") (pinfunction "6_6") (pintype "passive"))
    )
    (net (code "45") (name "Net-(J23-Pad1)") (class "Default")
      (node (ref "J23") (pin "1") (pinfunction "1_1") (pintype "passive"))
      (node (ref "J23") (pin "2") (pinfunction "2_2") (pintype "passive"))
      (node (ref "J23") (pin "3") (pinfunction "3_3") (pintype "passive"))
      (node (ref "J23") (pin "4") (pinfunction "4_4") (pintype "passive"))
      (node (ref "J23") (pin "5") (pinfunction "5_5") (pintype "passive"))
      (node (ref "J23") (pin "6") (pinfunction "6_6") (pintype "passive"))
    )
    (net (code "46") (name "Net-(J24-Pad1)") (class "Default")
      (node (ref "J24") (pin "1") (pinfunction "1_1") (pintype "passive"))
      (node (ref "J24") (pin "2") (pinfunction "2_2") (pintype "passive"))
      (node (ref "J24") (pin "3") (pinfunction "3_3") (pintype "passive"))
      (node (ref "J24") (pin "4") (pinfunction "4_4") (pintype "passive"))
      (node (ref "J24") (pin "5") (pinfunction "5_5") (pintype "passive"))
      (node (ref "J24") (pin "6") (pinfunction "6_6") (pintype "passive"))
    )
    (net (code "47") (name "Net-(J25-Pad1)") (class "Default")
      (node (ref "J25") (pin "1") (pinfunction "1_1") (pintype "passive"))
      (node (ref "J25") (pin "2") (pinfunction "2_2") (pintype "passive"))
      (node (ref "J25") (pin "3") (pinfunction "3_3") (pintype "passive"))
      (node (ref "J25") (pin "4") (pinfunction "4_4") (pintype "passive"))
      (node (ref "J25") (pin "5") (pinfunction "5_5") (pintype "passive"))
      (node (ref "J25") (pin "6") (pinfunction "6_6") (pintype "passive"))
    )
    (net (code "48") (name "Net-(J26-Pad1)") (class "Default")
      (node (ref "J26") (pin "1") (pinfunction "1_1") (pintype "passive"))
      (node (ref "J26") (pin "2") (pinfunction "2_2") (pintype "passive"))
      (node (ref "J26") (pin "3") (pinfunction "3_3") (pintype "passive"))
      (node (ref "J26") (pin "4") (pinfunction "4_4") (pintype "passive"))
      (node (ref "J26") (pin "5") (pinfunction "5_5") (pintype "passive"))
      (node (ref "J26") (pin "6") (pinfunction "6_6") (pintype "passive"))
    )
    (net (code "49") (name "Net-(J27-Pad1)") (class "Default")
      (node (ref "J27") (pin "1") (pinfunction "1_1") (pintype "passive"))
      (node (ref "J27") (pin "2") (pinfunction "2_2") (pintype "passive"))
      (node (ref "J27") (pin "3") (pinfunction "3_3") (pintype "passive"))
      (node (ref "J27") (pin "4") (pinfunction "4_4") (pintype "passive"))
      (node (ref "J27") (pin "5") (pinfunction "5_5") (pintype "passive"))
      (node (ref "J27") (pin "6") (pinfunction "6_6") (pintype "passive"))
    )
    (net (code "50") (name "Net-(J28-Pad1)") (class "Default")
      (node (ref "J28") (pin "1") (pinfunction "1_1") (pintype "passive"))
      (node (ref "J28") (pin "2") (pinfunction "2_2") (pintype "passive"))
      (node (ref "J28") (pin "3") (pinfunction "3_3") (pintype "passive"))
      (node (ref "J28") (pin "4") (pinfunction "4_4") (pintype "passive"))
      (node (ref "J28") (pin "5") (pinfunction "5_5") (pintype "passive"))
      (node (ref "J28") (pin "6") (pinfunction "6_6") (pintype "passive"))
    )
    (net (code "51") (name "Net-(J29-Pad1)") (class "Default")
      (node (ref "J29") (pin "1") (pinfunction "1_1") (pintype "passive"))
      (node (ref "J29") (pin "2") (pinfunction "2_2") (pintype "passive"))
      (node (ref "J29") (pin "3") (pinfunction "3_3") (pintype "passive"))
      (node (ref "J29") (pin "4") (pinfunction "4_4") (pintype "passive"))
      (node (ref "J29") (pin "5") (pinfunction "5_5") (pintype "passive"))
      (node (ref "J29") (pin "6") (pinfunction "6_6") (pintype "passive"))
    )
    (net (code "52") (name "Net-(J30-Pad1)") (class "Default")
      (node (ref "J30") (pin "1") (pinfunction "1_1") (pintype "passive"))
      (node (ref "J30") (pin "2") (pinfunction "2_2") (pintype "passive"))
      (node (ref "J30") (pin "3") (pinfunction "3_3") (pintype "passive"))
      (node (ref "J30") (pin "4") (pinfunction "4_4") (pintype "passive"))
      (node (ref "J30") (pin "5") (pinfunction "5_5") (pintype "passive"))
      (node (ref "J30") (pin "6") (pinfunction "6_6") (pintype "passive"))
    )
    (net (code "53") (name "Net-(J31-Pad1)") (class "Default")
      (node (ref "J31") (pin "1") (pinfunction "1_1") (pintype "passive"))
      (node (ref "J31") (pin "2") (pinfunction "2_2") (pintype "passive"))
      (node (ref "J31") (pin "3") (pinfunction "3_3") (pintype "passive"))
      (node (ref "J31") (pin "4") (pinfunction "4_4") (pintype "passive"))
      (node (ref "J31") (pin "5") (pinfunction "5_5") (pintype "passive"))
      (node (ref "J31") (pin "6") (pinfunction "6_6") (pintype "passive"))
    )
    (net (code "54") (name "Net-(J32-Pad1)") (class "Default")
      (node (ref "J32") (pin "1") (pinfunction "1_1") (pintype "passive"))
      (node (ref "J32") (pin "2") (pinfunction "2_2") (pintype "passive"))
      (node (ref "J32") (pin "3") (pinfunction "3_3") (pintype "passive"))
      (node (ref "J32") (pin "4") (pinfunction "4_4") (pintype "passive"))
      (node (ref "J32") (pin "5") (pinfunction "5_5") (pintype "passive"))
      (node (ref "J32") (pin "6") (pinfunction "6_6") (pintype "passive"))
    )
    (net (code "55") (name "Net-(J33-Pad1)") (class "Default")
      (node (ref "J33") (pin "1") (pinfunction "1_1") (pintype "passive"))
      (node (ref "J33") (pin "2") (pinfunction "2_2") (pintype "passive"))
      (node (ref "J33") (pin "3") (pinfunction "3_3") (pintype "passive"))
      (node (ref "J33") (pin "4") (pinfunction "4_4") (pintype "passive"))
      (node (ref "J33") (pin "5") (pinfunction "5_5") (pintype "passive"))
      (node (ref "J33") (pin "6") (pinfunction "6_6") (pintype "passive"))
    )
    (net (code "56") (name "Net-(J34-Pad1)") (class "Default")
      (node (ref "J34") (pin "1") (pinfunction "1_1") (pintype "passive"))
      (node (ref "J34") (pin "2") (pinfunction "2_2") (pintype "passive"))
      (node (ref "J34") (pin "3") (pinfunction "3_3") (pintype "passive"))
      (node (ref "J34") (pin "4") (pinfunction "4_4") (pintype "passive"))
      (node (ref "J34") (pin "5") (pinfunction "5_5") (pintype "passive"))
      (node (ref "J34") (pin "6") (pinfunction "6_6") (pintype "passive"))
    )
    (net (code "57") (name "Net-(J35-Pad1)") (class "Default")
      (node (ref "J35") (pin "1") (pinfunction "1_1") (pintype "passive"))
      (node (ref "J35") (pin "2") (pinfunction "2_2") (pintype "passive"))
      (node (ref "J35") (pin "3") (pinfunction "3_3") (pintype "passive"))
      (node (ref "J35") (pin "4") (pinfunction "4_4") (pintype "passive"))
      (node (ref "J35") (pin "5") (pinfunction "5_5") (pintype "passive"))
      (node (ref "J35") (pin "6") (pinfunction "6_6") (pintype "passive"))
    )
    (net (code "58") (name "Net-(J36-Pad1)") (class "Default")
      (node (ref "J36") (pin "1") (pinfunction "1_1") (pintype "passive"))
      (node (ref "J36") (pin "2") (pinfunction "2_2") (pintype "passive"))
      (node (ref "J36") (pin "3") (pinfunction "3_3") (pintype "passive"))
      (node (ref "J36") (pin "4") (pinfunction "4_4") (pintype "passive"))
      (node (ref "J36") (pin "5") (pinfunction "5_5") (pintype "passive"))
      (node (ref "J36") (pin "6") (pinfunction "6_6") (pintype "passive"))
    )
    (net (code "59") (name "Net-(J37-Pad1)") (class "Default")
      (node (ref "J37") (pin "1") (pinfunction "1_1") (pintype "passive"))
      (node (ref "J37") (pin "2") (pinfunction "2_2") (pintype "passive"))
      (node (ref "J37") (pin "3") (pinfunction "3_3") (pintype "passive"))
      (node (ref "J37") (pin "4") (pinfunction "4_4") (pintype "passive"))
      (node (ref "J37") (pin "5") (pinfunction "5_5") (pintype "passive"))
      (node (ref "J37") (pin "6") (pinfunction "6_6") (pintype "passive"))
    )
    (net (code "60") (name "Net-(J38-Pad1)") (class "Default")
      (node (ref "J38") (pin "1") (pinfunction "1_1") (pintype "passive"))
      (node (ref "J38") (pin "2") (pinfunction "2_2") (pintype "passive"))
      (node (ref "J38") (pin "3") (pinfunction "3_3") (pintype "passive"))
      (node (ref "J38") (pin "4") (pinfunction "4_4") (pintype "passive"))
      (node (ref "J38") (pin "5") (pinfunction "5_5") (pintype "passive"))
      (node (ref "J38") (pin "6") (pinfunction "6_6") (pintype "passive"))
    )
    (net (code "61") (name "Net-(J39-Pad1)") (class "Default")
      (node (ref "J39") (pin "1") (pinfunction "1_1") (pintype "passive"))
      (node (ref "J39") (pin "2") (pinfunction "2_2") (pintype "passive"))
      (node (ref "J39") (pin "3") (pinfunction "3_3") (pintype "passive"))
      (node (ref "J39") (pin "4") (pinfunction "4_4") (pintype "passive"))
      (node (ref "J39") (pin "5") (pinfunction "5_5") (pintype "passive"))
      (node (ref "J39") (pin "6") (pinfunction "6_6") (pintype "passive"))
    )
    (net (code "62") (name "Net-(J40-Pad1)") (class "Default")
      (node (ref "J40") (pin "1") (pinfunction "1_1") (pintype "passive"))
      (node (ref "J40") (pin "2") (pinfunction "2_2") (pintype "passive"))
      (node (ref "J40") (pin "3") (pinfunction "3_3") (pintype "passive"))
      (node (ref "J40") (pin "4") (pinfunction "4_4") (pintype "passive"))
      (node (ref "J40") (pin "5") (pinfunction "5_5") (pintype "passive"))
      (node (ref "J40") (pin "6") (pinfunction "6_6") (pintype "passive"))
    )
    (net (code "63") (name "Net-(J41-Pad1)") (class "Default")
      (node (ref "J41") (pin "1") (pinfunction "1_1") (pintype "passive"))
      (node (ref "J41") (pin "2") (pinfunction "2_2") (pintype "passive"))
      (node (ref "J41") (pin "3") (pinfunction "3_3") (pintype "passive"))
      (node (ref "J41") (pin "4") (pinfunction "4_4") (pintype "passive"))
      (node (ref "J41") (pin "5") (pinfunction "5_5") (pintype "passive"))
      (node (ref "J41") (pin "6") (pinfunction "6_6") (pintype "passive"))
    )
    (net (code "64") (name "Net-(J42-Pad1)") (class "Default")
      (node (ref "J42") (pin "1") (pinfunction "1_1") (pintype "passive"))
      (node (ref "J42") (pin "2") (pinfunction "2_2") (pintype "passive"))
      (node (ref "J42") (pin "3") (pinfunction "3_3") (pintype "passive"))
      (node (ref "J42") (pin "4") (pinfunction "4_4") (pintype "passive"))
      (node (ref "J42") (pin "5") (pinfunction "5_5") (pintype "passive"))
      (node (ref "J42") (pin "6") (pinfunction "6_6") (pintype "passive"))
    )
    (net (code "65") (name "Net-(J43-Pad1)") (class "Default")
      (node (ref "J43") (pin "1") (pinfunction "1_1") (pintype "passive"))
      (node (ref "J43") (pin "2") (pinfunction "2_2") (pintype "passive"))
      (node (ref "J43") (pin "3") (pinfunction "3_3") (pintype "passive"))
      (node (ref "J43") (pin "4") (pinfunction "4_4") (pintype "passive"))
      (node (ref "J43") (pin "5") (pinfunction "5_5") (pintype "passive"))
      (node (ref "J43") (pin "6") (pinfunction "6_6") (pintype "passive"))
    )
    (net (code "66") (name "Net-(J46-Pad1)") (class "Default")
      (node (ref "J46") (pin "1") (pinfunction "1_1") (pintype "passive"))
      (node (ref "J46") (pin "2") (pinfunction "2_2") (pintype "passive"))
      (node (ref "J46") (pin "3") (pinfunction "3_3") (pintype "passive"))
      (node (ref "J46") (pin "4") (pinfunction "4_4") (pintype "passive"))
      (node (ref "J46") (pin "5") (pinfunction "5_5") (pintype "passive"))
      (node (ref "J46") (pin "6") (pinfunction "6_6") (pintype "passive"))
    )
    (net (code "67") (name "Net-(J47-Pad1)") (class "Default")
      (node (ref "J47") (pin "1") (pinfunction "1_1") (pintype "passive"))
      (node (ref "J47") (pin "2") (pinfunction "2_2") (pintype "passive"))
      (node (ref "J47") (pin "3") (pinfunction "3_3") (pintype "passive"))
      (node (ref "J47") (pin "4") (pinfunction "4_4") (pintype "passive"))
      (node (ref "J47") (pin "5") (pinfunction "5_5") (pintype "passive"))
      (node (ref "J47") (pin "6") (pinfunction "6_6") (pintype "passive"))
    )
    (net (code "68") (name "Net-(J48-Pad1)") (class "Default")
      (node (ref "J48") (pin "1") (pinfunction "1_1") (pintype "passive"))
      (node (ref "J48") (pin "2") (pinfunction "2_2") (pintype "passive"))
      (node (ref "J48") (pin "3") (pinfunction "3_3") (pintype "passive"))
      (node (ref "J48") (pin "4") (pinfunction "4_4") (pintype "passive"))
      (node (ref "J48") (pin "5") (pinfunction "5_5") (pintype "passive"))
      (node (ref "J48") (pin "6") (pinfunction "6_6") (pintype "passive"))
    )
    (net (code "69") (name "Net-(J49-Pad1)") (class "Default")
      (node (ref "J49") (pin "1") (pinfunction "1_1") (pintype "passive"))
      (node (ref "J49") (pin "2") (pinfunction "2_2") (pintype "passive"))
      (node (ref "J49") (pin "3") (pinfunction "3_3") (pintype "passive"))
      (node (ref "J49") (pin "4") (pinfunction "4_4") (pintype "passive"))
      (node (ref "J49") (pin "5") (pinfunction "5_5") (pintype "passive"))
      (node (ref "J49") (pin "6") (pinfunction "6_6") (pintype "passive"))
    )
    (net (code "70") (name "Net-(J50-Pad1)") (class "Default")
      (node (ref "J50") (pin "1") (pinfunction "1_1") (pintype "passive"))
      (node (ref "J50") (pin "2") (pinfunction "2_2") (pintype "passive"))
      (node (ref "J50") (pin "3") (pinfunction "3_3") (pintype "passive"))
      (node (ref "J50") (pin "4") (pinfunction "4_4") (pintype "passive"))
      (node (ref "J50") (pin "5") (pinfunction "5_5") (pintype "passive"))
      (node (ref "J50") (pin "6") (pinfunction "6_6") (pintype "passive"))
    )
    (net (code "71") (name "Net-(J51-Pad1)") (class "Default")
      (node (ref "J51") (pin "1") (pinfunction "1_1") (pintype "passive"))
      (node (ref "J51") (pin "2") (pinfunction "2_2") (pintype "passive"))
      (node (ref "J51") (pin "3") (pinfunction "3_3") (pintype "passive"))
      (node (ref "J51") (pin "4") (pinfunction "4_4") (pintype "passive"))
      (node (ref "J51") (pin "5") (pinfunction "5_5") (pintype "passive"))
      (node (ref "J51") (pin "6") (pinfunction "6_6") (pintype "passive"))
    )
    (net (code "72") (name "Net-(J52-Pad1)") (class "Default")
      (node (ref "J52") (pin "1") (pinfunction "1_1") (pintype "passive"))
      (node (ref "J52") (pin "2") (pinfunction "2_2") (pintype "passive"))
      (node (ref "J52") (pin "3") (pinfunction "3_3") (pintype "passive"))
      (node (ref "J52") (pin "4") (pinfunction "4_4") (pintype "passive"))
      (node (ref "J52") (pin "5") (pinfunction "5_5") (pintype "passive"))
      (node (ref "J52") (pin "6") (pinfunction "6_6") (pintype "passive"))
    )
    (net (code "73") (name "Net-(J53-Pad1)") (class "Default")
      (node (ref "J53") (pin "1") (pinfunction "1_1") (pintype "passive"))
      (node (ref "J53") (pin "2") (pinfunction "2_2") (pintype "passive"))
      (node (ref "J53") (pin "3") (pinfunction "3_3") (pintype "passive"))
      (node (ref "J53") (pin "4") (pinfunction "4_4") (pintype "passive"))
      (node (ref "J53") (pin "5") (pinfunction "5_5") (pintype "passive"))
      (node (ref "J53") (pin "6") (pinfunction "6_6") (pintype "passive"))
    )
    (net (code "74") (name "Net-(J54-Pad1)") (class "Default")
      (node (ref "J54") (pin "1") (pinfunction "1_1") (pintype "passive"))
      (node (ref "J54") (pin "2") (pinfunction "2_2") (pintype "passive"))
      (node (ref "J54") (pin "3") (pinfunction "3_3") (pintype "passive"))
      (node (ref "J54") (pin "4") (pinfunction "4_4") (pintype "passive"))
      (node (ref "J54") (pin "5") (pinfunction "5_5") (pintype "passive"))
      (node (ref "J54") (pin "6") (pinfunction "6_6") (pintype "passive"))
    )
    (net (code "75") (name "Net-(J55-Pad1)") (class "Default")
      (node (ref "J55") (pin "1") (pinfunction "1_1") (pintype "passive"))
      (node (ref "J55") (pin "2") (pinfunction "2_2") (pintype "passive"))
      (node (ref "J55") (pin "3") (pinfunction "3_3") (pintype "passive"))
      (node (ref "J55") (pin "4") (pinfunction "4_4") (pintype "passive"))
      (node (ref "J55") (pin "5") (pinfunction "5_5") (pintype "passive"))
      (node (ref "J55") (pin "6") (pinfunction "6_6") (pintype "passive"))
    )
    (net (code "76") (name "Net-(J56-Pad1)") (class "Default")
      (node (ref "J56") (pin "1") (pinfunction "1_1") (pintype "passive"))
      (node (ref "J56") (pin "2") (pinfunction "2_2") (pintype "passive"))
      (node (ref "J56") (pin "3") (pinfunction "3_3") (pintype "passive"))
      (node (ref "J56") (pin "4") (pinfunction "4_4") (pintype "passive"))
      (node (ref "J56") (pin "5") (pinfunction "5_5") (pintype "passive"))
      (node (ref "J56") (pin "6") (pinfunction "6_6") (pintype "passive"))
    )
    (net (code "77") (name "Net-(J57-Pad1)") (class "Default")
      (node (ref "J57") (pin "1") (pinfunction "1_1") (pintype "passive"))
      (node (ref "J57") (pin "2") (pinfunction "2_2") (pintype "passive"))
      (node (ref "J57") (pin "3") (pinfunction "3_3") (pintype "passive"))
      (node (ref "J57") (pin "4") (pinfunction "4_4") (pintype "passive"))
      (node (ref "J57") (pin "5") (pinfunction "5_5") (pintype "passive"))
      (node (ref "J57") (pin "6") (pinfunction "6_6") (pintype "passive"))
    )
    (net (code "78") (name "Net-(J58-Pad1)") (class "Default")
      (node (ref "J58") (pin "1") (pinfunction "1_1") (pintype "passive"))
      (node (ref "J58") (pin "2") (pinfunction "2_2") (pintype "passive"))
      (node (ref "J58") (pin "3") (pinfunction "3_3") (pintype "passive"))
      (node (ref "J58") (pin "4") (pinfunction "4_4") (pintype "passive"))
      (node (ref "J58") (pin "5") (pinfunction "5_5") (pintype "passive"))
      (node (ref "J58") (pin "6") (pinfunction "6_6") (pintype "passive"))
    )
    (net (code "79") (name "Net-(J59-Pad1)") (class "Default")
      (node (ref "J59") (pin "1") (pinfunction "1_1") (pintype "passive"))
      (node (ref "J59") (pin "2") (pinfunction "2_2") (pintype "passive"))
      (node (ref "J59") (pin "3") (pinfunction "3_3") (pintype "passive"))
      (node (ref "J59") (pin "4") (pinfunction "4_4") (pintype "passive"))
      (node (ref "J59") (pin "5") (pinfunction "5_5") (pintype "passive"))
      (node (ref "J59") (pin "6") (pinfunction "6_6") (pintype "passive"))
    )
    (net (code "80") (name "Net-(J60-Pad1)") (class "Default")
      (node (ref "J60") (pin "1") (pinfunction "1_1") (pintype "passive"))
      (node (ref "J60") (pin "2") (pinfunction "2_2") (pintype "passive"))
      (node (ref "J60") (pin "3") (pinfunction "3_3") (pintype "passive"))
      (node (ref "J60") (pin "4") (pinfunction "4_4") (pintype "passive"))
      (node (ref "J60") (pin "5") (pinfunction "5_5") (pintype "passive"))
      (node (ref "J60") (pin "6") (pinfunction "6_6") (pintype "passive"))
    )
    (net (code "81") (name "Net-(J61-Pad1)") (class "Default")
      (node (ref "J61") (pin "1") (pinfunction "1_1") (pintype "passive"))
      (node (ref "J61") (pin "2") (pinfunction "2_2") (pintype "passive"))
      (node (ref "J61") (pin "3") (pinfunction "3_3") (pintype "passive"))
      (node (ref "J61") (pin "4") (pinfunction "4_4") (pintype "passive"))
      (node (ref "J61") (pin "5") (pinfunction "5_5") (pintype "passive"))
      (node (ref "J61") (pin "6") (pinfunction "6_6") (pintype "passive"))
    )
    (net (code "82") (name "Net-(J62-Pad1)") (class "Default")
      (node (ref "J62") (pin "1") (pinfunction "1_1") (pintype "passive"))
      (node (ref "J62") (pin "2") (pinfunction "2_2") (pintype "passive"))
      (node (ref "J62") (pin "3") (pinfunction "3_3") (pintype "passive"))
      (node (ref "J62") (pin "4") (pinfunction "4_4") (pintype "passive"))
      (node (ref "J62") (pin "5") (pinfunction "5_5") (pintype "passive"))
      (node (ref "J62") (pin "6") (pinfunction "6_6") (pintype "passive"))
    )
    (net (code "83") (name "Net-(J63-Pad1)") (class "Default")
      (node (ref "J63") (pin "1") (pinfunction "1_1") (pintype "passive"))
      (node (ref "J63") (pin "2") (pinfunction "2_2") (pintype "passive"))
      (node (ref "J63") (pin "3") (pinfunction "3_3") (pintype "passive"))
      (node (ref "J63") (pin "4") (pinfunction "4_4") (pintype "passive"))
      (node (ref "J63") (pin "5") (pinfunction "5_5") (pintype "passive"))
      (node (ref "J63") (pin "6") (pinfunction "6_6") (pintype "passive"))
    )
    (net (code "84") (name "Net-(J64-Pad1)") (class "Default")
      (node (ref "J64") (pin "1") (pinfunction "1_1") (pintype "passive"))
      (node (ref "J64") (pin "2") (pinfunction "2_2") (pintype "passive"))
      (node (ref "J64") (pin "3") (pinfunction "3_3") (pintype "passive"))
      (node (ref "J64") (pin "4") (pinfunction "4_4") (pintype "passive"))
      (node (ref "J64") (pin "5") (pinfunction "5_5") (pintype "passive"))
      (node (ref "J64") (pin "6") (pinfunction "6_6") (pintype "passive"))
    )
    (net (code "85") (name "Net-(J65-Pad1)") (class "Default")
      (node (ref "J65") (pin "1") (pinfunction "1_1") (pintype "passive"))
      (node (ref "J65") (pin "2") (pinfunction "2_2") (pintype "passive"))
      (node (ref "J65") (pin "3") (pinfunction "3_3") (pintype "passive"))
      (node (ref "J65") (pin "4") (pinfunction "4_4") (pintype "passive"))
      (node (ref "J65") (pin "5") (pinfunction "5_5") (pintype "passive"))
      (node (ref "J65") (pin "6") (pinfunction "6_6") (pintype "passive"))
    )
    (net (code "86") (name "Net-(J66-Pad1)") (class "Default")
      (node (ref "J66") (pin "1") (pinfunction "1_1") (pintype "passive"))
      (node (ref "J66") (pin "2") (pinfunction "2_2") (pintype "passive"))
      (node (ref "J66") (pin "3") (pinfunction "3_3") (pintype "passive"))
      (node (ref "J66") (pin "4") (pinfunction "4_4") (pintype "passive"))
      (node (ref "J66") (pin "5") (pinfunction "5_5") (pintype "passive"))
      (node (ref "J66") (pin "6") (pinfunction "6_6") (pintype "passive"))
    )
    (net (code "87") (name "Net-(J67-Pad1)") (class "Default")
      (node (ref "J67") (pin "1") (pinfunction "1_1") (pintype "passive"))
      (node (ref "J67") (pin "2") (pinfunction "2_2") (pintype "passive"))
      (node (ref "J67") (pin "3") (pinfunction "3_3") (pintype "passive"))
      (node (ref "J67") (pin "4") (pinfunction "4_4") (pintype "passive"))
      (node (ref "J67") (pin "5") (pinfunction "5_5") (pintype "passive"))
      (node (ref "J67") (pin "6") (pinfunction "6_6") (pintype "passive"))
    )
    (net (code "88") (name "Net-(J68-Pad1)") (class "Default")
      (node (ref "J68") (pin "1") (pinfunction "1_1") (pintype "passive"))
      (node (ref "J68") (pin "2") (pinfunction "2_2") (pintype "passive"))
      (node (ref "J68") (pin "3") (pinfunction "3_3") (pintype "passive"))
      (node (ref "J68") (pin "4") (pinfunction "4_4") (pintype "passive"))
      (node (ref "J68") (pin "5") (pinfunction "5_5") (pintype "passive"))
      (node (ref "J68") (pin "6") (pinfunction "6_6") (pintype "passive"))
    )
    (net (code "89") (name "Net-(J69-Pad1)") (class "Default")
      (node (ref "J69") (pin "1") (pinfunction "1_1") (pintype "passive"))
      (node (ref "J69") (pin "2") (pinfunction "2_2") (pintype "passive"))
      (node (ref "J69") (pin "3") (pinfunction "3_3") (pintype "passive"))
      (node (ref "J69") (pin "4") (pinfunction "4_4") (pintype "passive"))
      (node (ref "J69") (pin "5") (pinfunction "5_5") (pintype "passive"))
      (node (ref "J69") (pin "6") (pinfunction "6_6") (pintype "passive"))
    )
    (net (code "90") (name "Net-(J70-Pad1)") (class "Default")
      (node (ref "J70") (pin "1") (pinfunction "1_1") (pintype "passive"))
      (node (ref "J70") (pin "2") (pinfunction "2_2") (pintype "passive"))
      (node (ref "J70") (pin "3") (pinfunction "3_3") (pintype "passive"))
      (node (ref "J70") (pin "4") (pinfunction "4_4") (pintype "passive"))
      (node (ref "J70") (pin "5") (pinfunction "5_5") (pintype "passive"))
      (node (ref "J70") (pin "6") (pinfunction "6_6") (pintype "passive"))
    )
    (net (code "91") (name "Net-(J71-Pad1)") (class "Default")
      (node (ref "J71") (pin "1") (pinfunction "1_1") (pintype "passive"))
      (node (ref "J71") (pin "2") (pinfunction "2_2") (pintype "passive"))
      (node (ref "J71") (pin "3") (pinfunction "3_3") (pintype "passive"))
      (node (ref "J71") (pin "4") (pinfunction "4_4") (pintype "passive"))
      (node (ref "J71") (pin "5") (pinfunction "5_5") (pintype "passive"))
      (node (ref "J71") (pin "6") (pinfunction "6_6") (pintype "passive"))
    )
    (net (code "92") (name "Net-(J72-Pad1)") (class "Default")
      (node (ref "J72") (pin "1") (pinfunction "1_1") (pintype "passive"))
      (node (ref "J72") (pin "2") (pinfunction "2_2") (pintype "passive"))
      (node (ref "J72") (pin "3") (pinfunction "3_3") (pintype "passive"))
      (node (ref "J72") (pin "4") (pinfunction "4_4") (pintype "passive"))
      (node (ref "J72") (pin "5") (pinfunction "5_5") (pintype "passive"))
      (node (ref "J72") (pin "6") (pinfunction "6_6") (pintype "passive"))
    )
    (net (code "93") (name "Net-(J73-Pad1)") (class "Default")
      (node (ref "J73") (pin "1") (pinfunction "1_1") (pintype "passive"))
      (node (ref "J73") (pin "2") (pinfunction "2_2") (pintype "passive"))
      (node (ref "J73") (pin "3") (pinfunction "3_3") (pintype "passive"))
      (node (ref "J73") (pin "4") (pinfunction "4_4") (pintype "passive"))
      (node (ref "J73") (pin "5") (pinfunction "5_5") (pintype "passive"))
      (node (ref "J73") (pin "6") (pinfunction "6_6") (pintype "passive"))
    )
    (net (code "94") (name "Net-(J74-Pad1)") (class "Default")
      (node (ref "J74") (pin "1") (pinfunction "1_1") (pintype "passive"))
      (node (ref "J74") (pin "10") (pinfunction "10_10") (pintype "passive"))
      (node (ref "J74") (pin "11") (pinfunction "11_11") (pintype "passive"))
      (node (ref "J74") (pin "12") (pinfunction "12_12") (pintype "passive"))
      (node (ref "J74") (pin "13") (pinfunction "13_13") (pintype "passive"))
      (node (ref "J74") (pin "14") (pinfunction "14_14") (pintype "passive"))
      (node (ref "J74") (pin "15") (pinfunction "15_15") (pintype "passive"))
      (node (ref "J74") (pin "16") (pinfunction "16_16") (pintype "passive"))
      (node (ref "J74") (pin "17") (pinfunction "17_17") (pintype "passive"))
      (node (ref "J74") (pin "18") (pinfunction "18_18") (pintype "passive"))
      (node (ref "J74") (pin "19") (pinfunction "19_19") (pintype "passive"))
      (node (ref "J74") (pin "2") (pinfunction "2_2") (pintype "passive"))
      (node (ref "J74") (pin "20") (pinfunction "20_20") (pintype "passive"))
      (node (ref "J74") (pin "21") (pinfunction "21_21") (pintype "passive"))
      (node (ref "J74") (pin "22") (pinfunction "22_22") (pintype "passive"))
      (node (ref "J74") (pin "23") (pinfunction "23_23") (pintype "passive"))
      (node (ref "J74") (pin "24") (pinfunction "24_24") (pintype "passive"))
      (node (ref "J74") (pin "25") (pinfunction "25_25") (pintype "passive"))
      (node (ref "J74") (pin "26") (pinfunction "26_26") (pintype "passive"))
      (node (ref "J74") (pin "27") (pinfunction "27_27") (pintype "passive"))
      (node (ref "J74") (pin "28") (pinfunction "28_28") (pintype "passive"))
      (node (ref "J74") (pin "29") (pinfunction "29_29") (pintype "passive"))
      (node (ref "J74") (pin "3") (pinfunction "3_3") (pintype "passive"))
      (node (ref "J74") (pin "4") (pinfunction "4_4") (pintype "passive"))
      (node (ref "J74") (pin "5") (pinfunction "5_5") (pintype "passive"))
      (node (ref "J74") (pin "6") (pinfunction "6_6") (pintype "passive"))
      (node (ref "J74") (pin "7") (pinfunction "7_7") (pintype "passive"))
      (node (ref "J74") (pin "8") (pinfunction "8_8") (pintype "passive"))
      (node (ref "J74") (pin "9") (pinfunction "9_9") (pintype "passive"))
    )
    (net (code "95") (name "Net-(J75-Pad1)") (class "Default")
      (node (ref "J75") (pin "1") (pinfunction "1_1") (pintype "passive"))
      (node (ref "J75") (pin "2") (pinfunction "2_2") (pintype "passive"))
      (node (ref "J75") (pin "3") (pinfunction "3_3") (pintype "passive"))
      (node (ref "J75") (pin "4") (pinfunction "4_4") (pintype "passive"))
      (node (ref "J75") (pin "5") (pinfunction "5_5") (pintype "passive"))
    )
    (net (code "96") (name "Net-(J76-Pad1)") (class "Default")
      (node (ref "J76") (pin "1") (pinfunction "1_1") (pintype "passive"))
      (node (ref "J76") (pin "2") (pinfunction "2_2") (pintype "passive"))
      (node (ref "J76") (pin "3") (pinfunction "3_3") (pintype "passive"))
      (node (ref "J76") (pin "4") (pinfunction "4_4") (pintype "passive"))
      (node (ref "J76") (pin "5") (pinfunction "5_5") (pintype "passive"))
    )
    (net (code "97") (name "unconnected-(IC2-A5-Pad8)") (class "Default")
      (node (ref "IC2") (pin "8") (pinfunction "A5_8") (pintype "bidirectional"))
    )
    (net (code "98") (name "unconnected-(IC2-A6-Pad9)") (class "Default")
      (node (ref "IC2") (pin "9") (pinfunction "A6_9") (pintype "bidirectional"))
    )
    (net (code "99") (name "unconnected-(IC2-A7-Pad10)") (class "Default")
      (node (ref "IC2") (pin "10") (pinfunction "A7_10") (pintype "bidirectional"))
    )
    (net (code "100") (name "unconnected-(IC3-B0-Pad21)") (class "Default")
      (node (ref "IC3") (pin "21") (pinfunction "B0_21") (pintype "bidirectional"))
    )
    (net (code "101") (name "unconnected-(IC3-B1-Pad20)") (class "Default")
      (node (ref "IC3") (pin "20") (pinfunction "B1_20") (pintype "bidirectional"))
    )
    (net (code "102") (name "unconnected-(IC3-B2-Pad19)") (class "Default")
      (node (ref "IC3") (pin "19") (pinfunction "B2_19") (pintype "bidirectional"))
    )
    (net (code "103") (name "unconnected-(IC3-B3-Pad18)") (class "Default")
      (node (ref "IC3") (pin "18") (pinfunction "B3_18") (pintype "bidirectional"))
    )
    (net (code "104") (name "unconnected-(IC3-B4-Pad17)") (class "Default")
      (node (ref "IC3") (pin "17") (pinfunction "B4_17") (pintype "bidirectional"))
    )
    (net (code "105") (name "unconnected-(IC3-B5-Pad16)") (class "Default")
      (node (ref "IC3") (pin "16") (pinfunction "B5_16") (pintype "bidirectional"))
    )
    (net (code "106") (name "unconnected-(J5-Pad2)") (class "Default")
      (node (ref "J5") (pin "2") (pinfunction "2_2") (pintype "bidirectional"))
    )
    (net (code "107") (name "unconnected-(J5-Pad6)") (class "Default")
      (node (ref "J5") (pin "6") (pinfunction "6_6") (pintype "bidirectional"))
    )
    (net (code "108") (name "unconnected-(J13-11-Pad9)") (class "Default")
      (node (ref "J13") (pin "9") (pinfunction "11_9") (pintype "bidirectional"))
    )
    (net (code "109") (name "unconnected-(J13-12-Pad10)") (class "Default")
      (node (ref "J13") (pin "10") (pinfunction "12_10") (pintype "bidirectional"))
    )
    (net (code "110") (name "unconnected-(J13-13-Pad11)") (class "Default")
      (node (ref "J13") (pin "11") (pinfunction "13_11") (pintype "bidirectional"))
    )
  )
)
